# MP3.net
KiCad netlist of a schematic drawn in Altium Designer
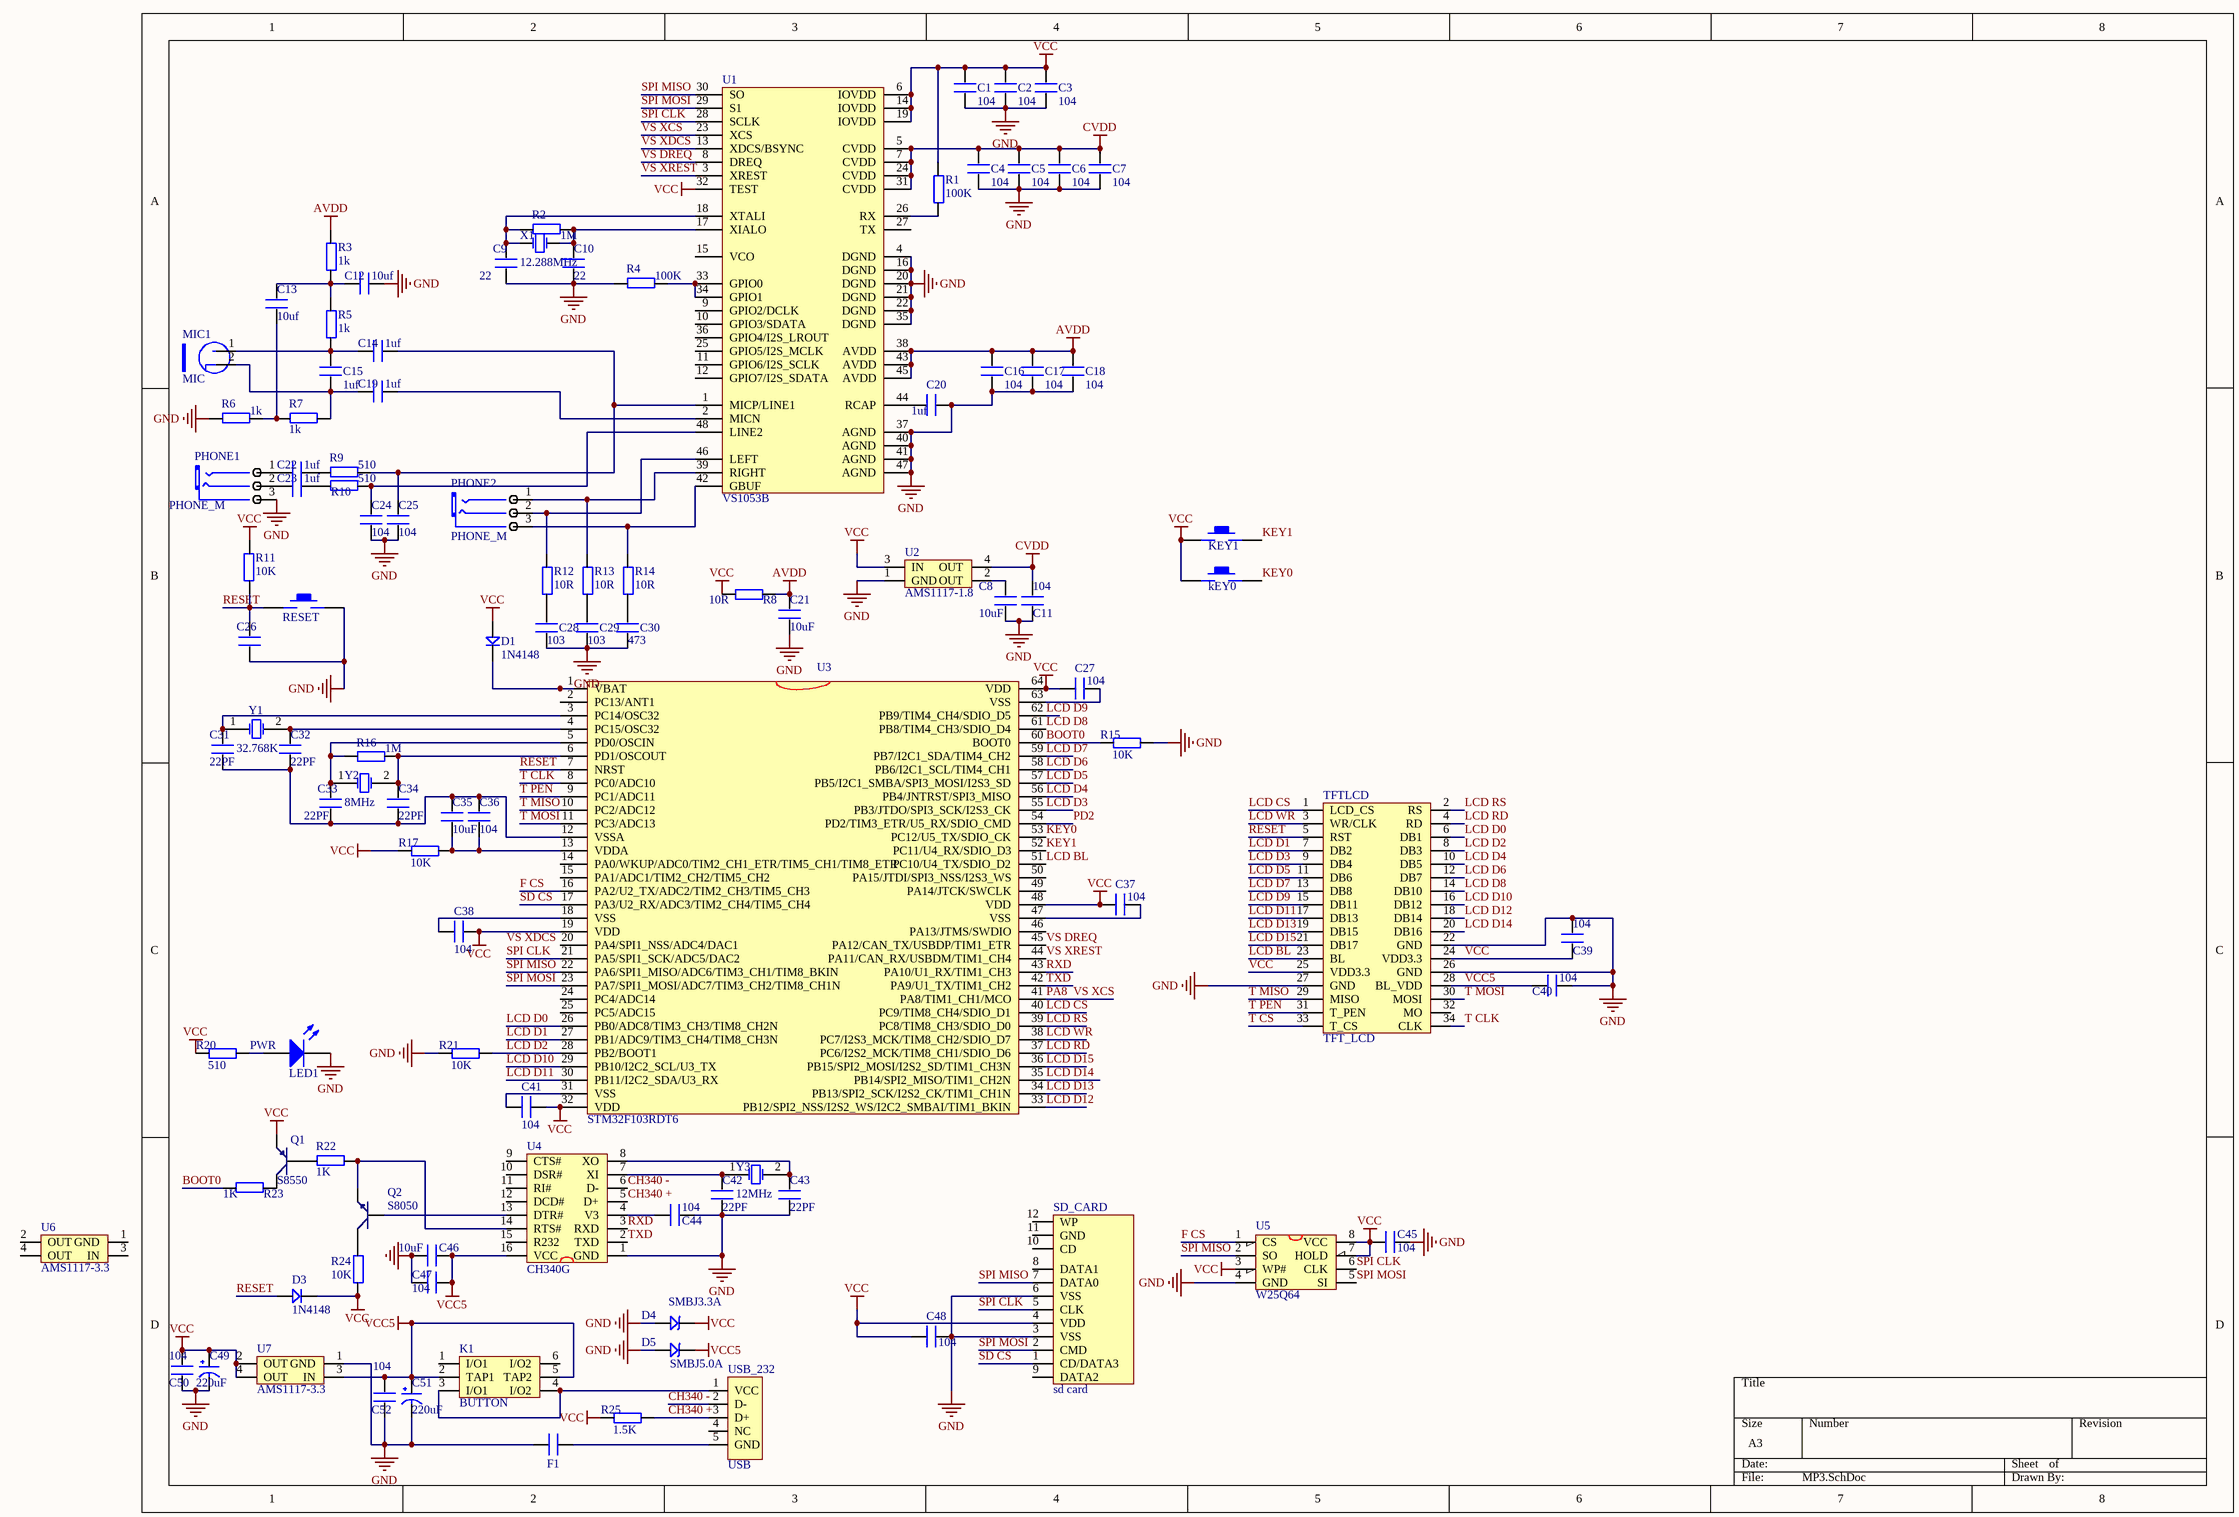
[diagram p0: MP3.SchDoc]

(export (version "E")
  (design (tool "Eeschema 10.0.6"))
  (components
    (comp (ref "C1") (value "104") (footprint "0603P") (libsource (lib "ATK-VS1053 MP3") (part "C")))
    (comp (ref "C2") (value "104") (footprint "0603P") (libsource (lib "ATK-VS1053 MP3") (part "C")))
    (comp (ref "C3") (value "104") (footprint "0603P") (libsource (lib "ATK-VS1053 MP3") (part "C")))
    (comp (ref "C4") (value "104") (footprint "0603P") (libsource (lib "ATK-VS1053 MP3") (part "C")))
    (comp (ref "C5") (value "104") (footprint "0603P") (libsource (lib "ATK-VS1053 MP3") (part "C")))
    (comp (ref "C6") (value "104") (footprint "0603P") (libsource (lib "ATK-VS1053 MP3") (part "C")))
    (comp (ref "C7") (value "104") (footprint "0603P") (libsource (lib "ATK-VS1053 MP3") (part "C")))
    (comp (ref "C8") (value "10uF") (footprint "0603P") (libsource (lib "ATK-MPU6050六轴传感器模块") (part "C")))
    (comp (ref "C9") (value "22") (footprint "0603P") (libsource (lib "ATK-VS1053 MP3") (part "C")))
    (comp (ref "C10") (value "22") (footprint "0603P") (libsource (lib "ATK-VS1053 MP3") (part "C")))
    (comp (ref "C11") (value "104") (footprint "0603P") (libsource (lib "ATK-MPU6050六轴传感器模块") (part "C")))
    (comp (ref "C12") (value "10uf") (footprint "0603P") (libsource (lib "ATK-VS1053 MP3") (part "C")))
    (comp (ref "C13") (value "10uf") (footprint "0603P") (libsource (lib "ATK-VS1053 MP3") (part "C")))
    (comp (ref "C14") (value "1uf") (footprint "0603P") (libsource (lib "ATK-VS1053 MP3") (part "C")))
    (comp (ref "C15") (value "1uf") (footprint "0603P") (libsource (lib "ATK-VS1053 MP3") (part "C")))
    (comp (ref "C16") (value "104") (footprint "0603P") (libsource (lib "ATK-VS1053 MP3") (part "C")))
    (comp (ref "C17") (value "104") (footprint "0603P") (libsource (lib "ATK-VS1053 MP3") (part "C")))
    (comp (ref "C18") (value "104") (footprint "0603P") (libsource (lib "ATK-VS1053 MP3") (part "C")))
    (comp (ref "C19") (value "1uf") (footprint "0603P") (libsource (lib "ATK-VS1053 MP3") (part "C")))
    (comp (ref "C20") (value "1uf") (footprint "0603P") (libsource (lib "ATK-VS1053 MP3") (part "C")))
    (comp (ref "C21") (value "10uF") (footprint "0603P") (libsource (lib "ATK-MPU6050六轴传感器模块") (part "C")))
    (comp (ref "C22") (value "1uf") (footprint "0603P") (libsource (lib "ATK-VS1053 MP3") (part "C")))
    (comp (ref "C23") (value "1uf") (footprint "0603P") (libsource (lib "ATK-VS1053 MP3") (part "C")))
    (comp (ref "C24") (value "104") (footprint "0603P") (libsource (lib "ATK-VS1053 MP3") (part "C")))
    (comp (ref "C25") (value "104") (footprint "0603P") (libsource (lib "ATK-VS1053 MP3") (part "C")))
    (comp (ref "C26") (value "10uF") (footprint "0603P") (libsource (lib "ATK-MPU6050六轴传感器模块") (part "C")))
    (comp (ref "C27") (value "104") (footprint "0603P") (libsource (lib "ATK-MPU6050六轴传感器模块") (part "C")))
    (comp (ref "C28") (value "103") (footprint "0603P") (libsource (lib "ATK-VS1053 MP3") (part "C")))
    (comp (ref "C29") (value "103") (footprint "0603P") (libsource (lib "ATK-VS1053 MP3") (part "C")))
    (comp (ref "C30") (value "473") (footprint "0603P") (libsource (lib "ATK-VS1053 MP3") (part "C")))
    (comp (ref "C31") (value "22PF") (footprint "0603P") (libsource (lib "ATK-MPU6050六轴传感器模块") (part "C")))
    (comp (ref "C32") (value "22PF") (footprint "0603P") (libsource (lib "ATK-MPU6050六轴传感器模块") (part "C")))
    (comp (ref "C33") (value "22PF") (footprint "0603P") (libsource (lib "ATK-MPU6050六轴传感器模块") (part "C")))
    (comp (ref "C34") (value "22PF") (footprint "0603P") (libsource (lib "ATK-MPU6050六轴传感器模块") (part "C")))
    (comp (ref "C35") (value "10uF") (footprint "0603P") (libsource (lib "ATK-MPU6050六轴传感器模块") (part "C")))
    (comp (ref "C36") (value "104") (footprint "0603P") (libsource (lib "ATK-MPU6050六轴传感器模块") (part "C")))
    (comp (ref "C37") (value "104") (footprint "0603P") (libsource (lib "ATK-MPU6050六轴传感器模块") (part "C")))
    (comp (ref "C38") (value "104") (footprint "0603P") (libsource (lib "ATK-MPU6050六轴传感器模块") (part "C")))
    (comp (ref "C39") (value "104") (footprint "0603P") (libsource (lib "ATK-MPU6050六轴传感器模块") (part "C")))
    (comp (ref "C40") (value "104") (footprint "0603P") (libsource (lib "ATK-MPU6050六轴传感器模块") (part "C")))
    (comp (ref "C41") (value "104") (footprint "0603P") (libsource (lib "ATK-MPU6050六轴传感器模块") (part "C")))
    (comp (ref "C42") (value "22PF") (footprint "0603P") (libsource (lib "ATK-MPU6050六轴传感器模块") (part "C")))
    (comp (ref "C43") (value "22PF") (footprint "0603P") (libsource (lib "ATK-MPU6050六轴传感器模块") (part "C")))
    (comp (ref "C44") (value "104") (footprint "0603P") (libsource (lib "ATK-MPU6050六轴传感器模块") (part "C")))
    (comp (ref "C45") (value "104") (footprint "0603P") (libsource (lib "ATK-MPU6050六轴传感器模块") (part "C")))
    (comp (ref "C46") (value "10uF") (footprint "0603P") (libsource (lib "ATK-MPU6050六轴传感器模块") (part "C")))
    (comp (ref "C47") (value "104") (footprint "0603P") (libsource (lib "MiniSTM32 V3.0封装库") (part "C")))
    (comp (ref "C48") (value "104") (footprint "0603P") (libsource (lib "ATK-MPU6050六轴传感器模块") (part "C")))
    (comp (ref "C49")
      (value "220uF")
      (footprint "CC6.56.5")
      (libsource (lib "MiniSTM32 V3.0封装库") (part "CAP"))
    )
    (comp (ref "C50") (value "104") (footprint "0603P") (libsource (lib "ATK-MPU6050六轴传感器模块") (part "C")))
    (comp (ref "C51")
      (value "220uF")
      (footprint "CC6.56.5")
      (libsource (lib "MiniSTM32 V3.0封装库") (part "CAP"))
    )
    (comp (ref "C52") (value "104") (footprint "0603P") (libsource (lib "ATK-MPU6050六轴传感器模块") (part "C")))
    (comp (ref "D1")
      (value "1N4148")
      (footprint "DIODE_SOP")
      (libsource (lib "MiniSTM32 V3.0封装库") (part "D"))
    )
    (comp (ref "D3")
      (value "1N4148")
      (footprint "DIODE_SOP")
      (libsource (lib "MiniSTM32 V3.0封装库") (part "D"))
    )
    (comp (ref "D4")
      (value "SMBJ3.3A")
      (footprint "SMBJ")
      (description "TVS")
      (libsource (lib "MiniSTM32 V3.0封装库") (part "SMBJ"))
    )
    (comp (ref "D5")
      (value "SMBJ5.0A")
      (footprint "SMBJ")
      (description "TVS")
      (libsource (lib "MiniSTM32 V3.0封装库") (part "SMBJ"))
    )
    (comp (ref "F1") (value "104") (footprint "0603P") (libsource (lib "MiniSTM32 V3.0封装库") (part "C")))
    (comp (ref "K1")
      (value "BUTTON")
      (footprint "BTN8.5*8.5")
      (libsource (lib "MiniSTM32 V3.0封装库") (part "BUTTON"))
    )
    (comp (ref "kEY0")
      (value "KEY_M")
      (footprint "KEY_M")
      (libsource (lib "MiniSTM32 V3.0封装库") (part "KEY_M"))
    )
    (comp (ref "KEY1")
      (value "KEY_M")
      (footprint "KEY_M")
      (libsource (lib "MiniSTM32 V3.0封装库") (part "KEY_M"))
    )
    (comp (ref "MIC1") (value "MIC") (footprint "MIC") (libsource (lib "ATK-VS1053 MP3") (part "MIC")))
    (comp (ref "PHONE1")
      (value "PHONE_M")
      (footprint "PHONE_ST")
      (libsource (lib "ATK-VS1053 MP3") (part "PHONE_M"))
    )
    (comp (ref "PHONE2")
      (value "PHONE_M")
      (footprint "PHONE_ST")
      (libsource (lib "ATK-VS1053 MP3") (part "PHONE_M"))
    )
    (comp (ref "PWR")
      (value "LED1")
      (footprint "SMDLED")
      (description "Typical RED, GREEN, YELLOW, AMBER GaAs LED")
      (fields (field (name "PUBLISHER") "Altium Limited"))
      (libsource (lib "MiniSTM32 V3.0封装库") (part "LED2"))
    )
    (comp (ref "Q1")
      (value "S8550")
      (footprint "SOT-23R")
      (description "8550/BCW68")
      (libsource (lib "MiniSTM32 V3.0封装库") (part "PNP"))
    )
    (comp (ref "Q2")
      (value "S8050")
      (footprint "SOT-23R")
      (description "8050/BCW846/BCW847")
      (libsource (lib "MiniSTM32 V3.0封装库") (part "NPN"))
    )
    (comp (ref "R1") (value "100K") (footprint "0603P") (libsource (lib "ATK-MPU6050六轴传感器模块") (part "R")))
    (comp (ref "R2") (value "1M") (footprint "0603P") (libsource (lib "ATK-MPU6050六轴传感器模块") (part "R")))
    (comp (ref "R3") (value "1k") (footprint "0603P") (libsource (lib "ATK-MPU6050六轴传感器模块") (part "R")))
    (comp (ref "R4") (value "100K") (footprint "0603P") (libsource (lib "ATK-MPU6050六轴传感器模块") (part "R")))
    (comp (ref "R5") (value "1k") (footprint "0603P") (libsource (lib "ATK-MPU6050六轴传感器模块") (part "R")))
    (comp (ref "R6") (value "1k") (footprint "0603P") (libsource (lib "ATK-MPU6050六轴传感器模块") (part "R")))
    (comp (ref "R7") (value "1k") (footprint "0603P") (libsource (lib "ATK-MPU6050六轴传感器模块") (part "R")))
    (comp (ref "R8") (value "10R") (footprint "0603P") (libsource (lib "ATK-MPU6050六轴传感器模块") (part "R")))
    (comp (ref "R9") (value "510") (footprint "0603P") (libsource (lib "ATK-MPU6050六轴传感器模块") (part "R")))
    (comp (ref "R10") (value "510") (footprint "0603P") (libsource (lib "ATK-MPU6050六轴传感器模块") (part "R")))
    (comp (ref "R11") (value "10K") (footprint "0603P") (libsource (lib "ATK-MPU6050六轴传感器模块") (part "R")))
    (comp (ref "R12") (value "10R") (footprint "0603P") (libsource (lib "ATK-MPU6050六轴传感器模块") (part "R")))
    (comp (ref "R13") (value "10R") (footprint "0603P") (libsource (lib "ATK-MPU6050六轴传感器模块") (part "R")))
    (comp (ref "R14") (value "10R") (footprint "0603P") (libsource (lib "ATK-MPU6050六轴传感器模块") (part "R")))
    (comp (ref "R15") (value "10K") (footprint "0603P") (libsource (lib "ATK-MPU6050六轴传感器模块") (part "R")))
    (comp (ref "R16") (value "1M") (footprint "0603P") (libsource (lib "MiniSTM32 V3.0封装库") (part "R")))
    (comp (ref "R17") (value "10K") (footprint "0603P") (libsource (lib "ATK-MPU6050六轴传感器模块") (part "R")))
    (comp (ref "R20") (value "510") (footprint "0603P") (libsource (lib "ATK-MPU6050六轴传感器模块") (part "R")))
    (comp (ref "R21") (value "10K") (footprint "0603P") (libsource (lib "ATK-MPU6050六轴传感器模块") (part "R")))
    (comp (ref "R22") (value "1K") (footprint "0603P") (libsource (lib "ATK-MPU6050六轴传感器模块") (part "R")))
    (comp (ref "R23") (value "1K") (footprint "0603P") (libsource (lib "ATK-MPU6050六轴传感器模块") (part "R")))
    (comp (ref "R24") (value "10K") (footprint "0603P") (libsource (lib "ATK-MPU6050六轴传感器模块") (part "R")))
    (comp (ref "R25") (value "1.5K") (footprint "0603P") (libsource (lib "ATK-MPU6050六轴传感器模块") (part "R")))
    (comp (ref "RESET")
      (value "KEY_M")
      (footprint "KEY_M")
      (libsource (lib "MiniSTM32 V3.0封装库") (part "KEY_M"))
    )
    (comp (ref "SD_CARD")
      (value "sd card")
      (footprint "SDCARD_L")
      (libsource (lib "MiniSTM32 V3.0封装库") (part "sd card"))
    )
    (comp (ref "TFTLCD")
      (value "TFT_LCD")
      (footprint "HDR2X17")
      (libsource (lib "MiniSTM32 V3.0封装库") (part "TFT_LCD"))
    )
    (comp (ref "U1")
      (value "VS1053B")
      (footprint "mTQFP48")
      (libsource (lib "ATK-VS1053 MP3") (part "VS1053"))
    )
    (comp (ref "U2")
      (value "AMS1117-1.8")
      (footprint "AMS1117")
      (libsource (lib "ATK-VS1053 MP3") (part "AMS1117"))
    )
    (comp (ref "U3")
      (value "STM32F103RDT6")
      (footprint "LQFP64")
      (libsource (lib "stm32") (part "STM32F103RDT6"))
    )
    (comp (ref "U4")
      (value "CH340G")
      (footprint "SOP16M")
      (description "USB2UART")
      (libsource (lib "MiniSTM32 V3.0封装库") (part "CH340G"))
    )
    (comp (ref "U5")
      (value "W25Q64")
      (footprint "SOIC-8")
      (description "W25X16;SST25VF016;MX25L1605")
      (libsource (lib "MiniSTM32 V3.0封装库") (part "W25X16"))
    )
    (comp (ref "U6")
      (value "AMS1117-3.3")
      (footprint "AMS1117")
      (libsource (lib "MiniSTM32 V3.0封装库") (part "AMS1117"))
    )
    (comp (ref "U7")
      (value "AMS1117-3.3")
      (footprint "AMS1117")
      (libsource (lib "MiniSTM32 V3.0封装库") (part "AMS1117"))
    )
    (comp (ref "USB_232")
      (value "USB")
      (footprint "USB/SM0.8-6H5")
      (libsource (lib "MiniSTM32 V3.0封装库") (part "USB5"))
    )
    (comp (ref "X1")
      (value "12.288MHz")
      (footprint "XTAL_US")
      (description "Crystal Oscillator")
      (fields (field (name "PUBLISHER") "Altium Limited"))
      (libsource (lib "ATK-VS1053 MP3") (part "XTAL"))
    )
    (comp (ref "Y1")
      (value "32.768K")
      (footprint "R38")
      (description "Crystal Oscillator")
      (fields (field (name "PUBLISHER") "Altium Limited"))
      (libsource (lib "Miscellaneous Devices") (part "XTAL"))
    )
    (comp (ref "Y2")
      (value "8MHz")
      (footprint "XTAL_US")
      (description "Crystal Oscillator")
      (fields (field (name "PUBLISHER") "Altium Limited"))
      (libsource (lib "MiniSTM32 V3.0封装库") (part "XTAL"))
    )
    (comp (ref "Y3")
      (value "12MHz")
      (footprint "XTAL_US")
      (description "Crystal Oscillator")
      (fields (field (name "PUBLISHER") "Altium Limited"))
      (libsource (lib "MiniSTM32 V3.0封装库") (part "XTAL"))
    )
  )
  (nets
    (net (code "1") (name "/BOOT0") (class "Default")
      (node (ref "R15") (pin "1") (pintype "passive"))
      (node (ref "R23") (pin "2") (pintype "passive"))
      (node (ref "U3") (pin "60") (pinfunction "BOOT0_60") (pintype "passive"))
    )
    (net (code "2") (name "/CH340 +") (class "Default")
      (node (ref "R25") (pin "2") (pintype "passive"))
      (node (ref "U4") (pin "5") (pinfunction "D+_5") (pintype "passive"))
      (node (ref "USB_232") (pin "3") (pinfunction "D+_3") (pintype "passive"))
    )
    (net (code "3") (name "/CH340 -") (class "Default")
      (node (ref "U4") (pin "6") (pinfunction "D-_6") (pintype "passive"))
      (node (ref "USB_232") (pin "2") (pinfunction "D-_2") (pintype "passive"))
    )
    (net (code "4") (name "/F CS") (class "Default")
      (node (ref "U3") (pin "16") (pinfunction "PA2/U2_TX/ADC2/TIM2_CH3/TIM5_CH3_16") (pintype "passive"))
      (node (ref "U5") (pin "1") (pinfunction "CS_1") (pintype "passive"))
    )
    (net (code "5") (name "/KEY0") (class "Default")
      (node (ref "U3") (pin "53") (pinfunction "PC12/U5_TX/SDIO_CK_53") (pintype "passive"))
      (node (ref "kEY0") (pin "2") (pinfunction "2_2") (pintype "passive"))
    )
    (net (code "6") (name "/KEY1") (class "Default")
      (node (ref "KEY1") (pin "2") (pinfunction "2_2") (pintype "passive"))
      (node (ref "U3") (pin "52") (pinfunction "PC11/U4_RX/SDIO_D3_52") (pintype "passive"))
    )
    (net (code "7") (name "/LCD BL") (class "Default")
      (node (ref "TFTLCD") (pin "23") (pinfunction "BL_23") (pintype "passive"))
      (node (ref "U3") (pin "51") (pinfunction "PC10/U4_TX/SDIO_D2_51") (pintype "passive"))
    )
    (net (code "8") (name "/LCD CS") (class "Default")
      (node (ref "TFTLCD") (pin "1") (pinfunction "LCD_CS_1") (pintype "passive"))
      (node (ref "U3") (pin "40") (pinfunction "PC9/TIM8_CH4/SDIO_D1_40") (pintype "passive"))
    )
    (net (code "9") (name "/LCD D0") (class "Default")
      (node (ref "TFTLCD") (pin "6") (pinfunction "DB1_6") (pintype "passive"))
      (node (ref "U3") (pin "26") (pinfunction "PB0/ADC8/TIM3_CH3/TIM8_CH2N_26") (pintype "passive"))
    )
    (net (code "10") (name "/LCD D1") (class "Default")
      (node (ref "TFTLCD") (pin "7") (pinfunction "DB2_7") (pintype "passive"))
      (node (ref "U3") (pin "27") (pinfunction "PB1/ADC9/TIM3_CH4/TIM8_CH3N_27") (pintype "passive"))
    )
    (net (code "11") (name "/LCD D2") (class "Default")
      (node (ref "R21") (pin "2") (pintype "passive"))
      (node (ref "TFTLCD") (pin "8") (pinfunction "DB3_8") (pintype "passive"))
      (node (ref "U3") (pin "28") (pinfunction "PB2/BOOT1_28") (pintype "passive"))
    )
    (net (code "12") (name "/LCD D3") (class "Default")
      (node (ref "TFTLCD") (pin "9") (pinfunction "DB4_9") (pintype "passive"))
      (node (ref "U3") (pin "55") (pinfunction "PB3/JTDO/SPI3_SCK/I2S3_CK_55") (pintype "passive"))
    )
    (net (code "13") (name "/LCD D4") (class "Default")
      (node (ref "TFTLCD") (pin "10") (pinfunction "DB5_10") (pintype "passive"))
      (node (ref "U3") (pin "56") (pinfunction "PB4/JNTRST/SPI3_MISO_56") (pintype "passive"))
    )
    (net (code "14") (name "/LCD D5") (class "Default")
      (node (ref "TFTLCD") (pin "11") (pinfunction "DB6_11") (pintype "passive"))
      (node (ref "U3") (pin "57") (pinfunction "PB5/I2C1_SMBA/SPI3_MOSI/I2S3_SD_57") (pintype "passive"))
    )
    (net (code "15") (name "/LCD D6") (class "Default")
      (node (ref "TFTLCD") (pin "12") (pinfunction "DB7_12") (pintype "passive"))
      (node (ref "U3") (pin "58") (pinfunction "PB6/I2C1_SCL/TIM4_CH1_58") (pintype "passive"))
    )
    (net (code "16") (name "/LCD D7") (class "Default")
      (node (ref "TFTLCD") (pin "13") (pinfunction "DB8_13") (pintype "passive"))
      (node (ref "U3") (pin "59") (pinfunction "PB7/I2C1_SDA/TIM4_CH2_59") (pintype "passive"))
    )
    (net (code "17") (name "/LCD D8") (class "Default")
      (node (ref "TFTLCD") (pin "14") (pinfunction "DB10_14") (pintype "passive"))
      (node (ref "U3") (pin "61") (pinfunction "PB8/TIM4_CH3/SDIO_D4_61") (pintype "passive"))
    )
    (net (code "18") (name "/LCD D9") (class "Default")
      (node (ref "TFTLCD") (pin "15") (pinfunction "DB11_15") (pintype "passive"))
      (node (ref "U3") (pin "62") (pinfunction "PB9/TIM4_CH4/SDIO_D5_62") (pintype "passive"))
    )
    (net (code "19") (name "/LCD D10") (class "Default")
      (node (ref "TFTLCD") (pin "16") (pinfunction "DB12_16") (pintype "passive"))
      (node (ref "U3") (pin "29") (pinfunction "PB10/I2C2_SCL/U3_TX_29") (pintype "passive"))
    )
    (net (code "20") (name "/LCD D11") (class "Default")
      (node (ref "TFTLCD") (pin "17") (pinfunction "DB13_17") (pintype "passive"))
      (node (ref "U3") (pin "30") (pinfunction "PB11/I2C2_SDA/U3_RX_30") (pintype "passive"))
    )
    (net (code "21") (name "/LCD D12") (class "Default")
      (node (ref "TFTLCD") (pin "18") (pinfunction "DB14_18") (pintype "passive"))
      (node (ref "U3") (pin "33") (pinfunction "PB12/SPI2_NSS/I2S2_WS/I2C2_SMBAI/TIM1_BKIN_33") (pintype "passive"))
    )
    (net (code "22") (name "/LCD D13") (class "Default")
      (node (ref "TFTLCD") (pin "19") (pinfunction "DB15_19") (pintype "passive"))
      (node (ref "U3") (pin "34") (pinfunction "PB13/SPI2_SCK/I2S2_CK/TIM1_CH1N_34") (pintype "passive"))
    )
    (net (code "23") (name "/LCD D14") (class "Default")
      (node (ref "TFTLCD") (pin "20") (pinfunction "DB16_20") (pintype "passive"))
      (node (ref "U3") (pin "35") (pinfunction "PB14/SPI2_MISO/TIM1_CH2N_35") (pintype "passive"))
    )
    (net (code "24") (name "/LCD D15") (class "Default")
      (node (ref "TFTLCD") (pin "21") (pinfunction "DB17_21") (pintype "passive"))
      (node (ref "U3") (pin "36") (pinfunction "PB15/SPI2_MOSI/I2S2_SD/TIM1_CH3N_36") (pintype "passive"))
    )
    (net (code "25") (name "/LCD RD") (class "Default")
      (node (ref "TFTLCD") (pin "4") (pinfunction "RD_4") (pintype "passive"))
      (node (ref "U3") (pin "37") (pinfunction "PC6/I2S2_MCK/TIM8_CH1/SDIO_D6_37") (pintype "passive"))
    )
    (net (code "26") (name "/LCD RS") (class "Default")
      (node (ref "TFTLCD") (pin "2") (pinfunction "RS_2") (pintype "passive"))
      (node (ref "U3") (pin "39") (pinfunction "PC8/TIM8_CH3/SDIO_D0_39") (pintype "passive"))
    )
    (net (code "27") (name "/LCD WR") (class "Default")
      (node (ref "TFTLCD") (pin "3") (pinfunction "WR/CLK_3") (pintype "passive"))
      (node (ref "U3") (pin "38") (pinfunction "PC7/I2S3_MCK/TIM8_CH2/SDIO_D7_38") (pintype "passive"))
    )
    (net (code "28") (name "/PA8") (class "Default")
      (node (ref "U1") (pin "23") (pinfunction "XCS_23") (pintype "passive"))
      (node (ref "U3") (pin "41") (pinfunction "PA8/TIM1_CH1/MCO_41") (pintype "passive"))
    )
    (net (code "29") (name "/PD2") (class "Default")
      (node (ref "U3") (pin "54") (pinfunction "PD2/TIM3_ETR/U5_RX/SDIO_CMD_54") (pintype "passive"))
    )
    (net (code "30") (name "/RESET") (class "Default")
      (node (ref "C26") (pin "2") (pintype "passive"))
      (node (ref "D3") (pin "1") (pintype "passive"))
      (node (ref "R11") (pin "2") (pintype "passive"))
      (node (ref "RESET") (pin "1") (pinfunction "1_1") (pintype "passive"))
      (node (ref "TFTLCD") (pin "5") (pinfunction "RST_5") (pintype "passive"))
      (node (ref "U3") (pin "7") (pinfunction "NRST_7") (pintype "passive"))
    )
    (net (code "31") (name "/RXD") (class "Default")
      (node (ref "U3") (pin "43") (pinfunction "PA10/U1_RX/TIM1_CH3_43") (pintype "passive"))
      (node (ref "U4") (pin "3") (pinfunction "RXD_3") (pintype "passive"))
    )
    (net (code "32") (name "/SD CS") (class "Default")
      (node (ref "SD_CARD") (pin "1") (pinfunction "CD/DATA3_1") (pintype "passive"))
      (node (ref "U3") (pin "17") (pinfunction "PA3/U2_RX/ADC3/TIM2_CH4/TIM5_CH4_17") (pintype "passive"))
    )
    (net (code "33") (name "/SPI CLK") (class "Default")
      (node (ref "SD_CARD") (pin "5") (pinfunction "CLK_5") (pintype "passive"))
      (node (ref "U1") (pin "28") (pinfunction "SCLK_28") (pintype "passive"))
      (node (ref "U3") (pin "21") (pinfunction "PA5/SPI1_SCK/ADC5/DAC2_21") (pintype "passive"))
      (node (ref "U5") (pin "6") (pinfunction "CLK_6") (pintype "passive"))
    )
    (net (code "34") (name "/SPI MISO") (class "Default")
      (node (ref "SD_CARD") (pin "7") (pinfunction "DATA0_7") (pintype "passive"))
      (node (ref "U1") (pin "30") (pinfunction "SO_30") (pintype "passive"))
      (node (ref "U3") (pin "22") (pinfunction "PA6/SPI1_MISO/ADC6/TIM3_CH1/TIM8_BKIN_22") (pintype "passive"))
      (node (ref "U5") (pin "2") (pinfunction "SO_2") (pintype "passive"))
    )
    (net (code "35") (name "/SPI MOSI") (class "Default")
      (node (ref "SD_CARD") (pin "2") (pinfunction "CMD_2") (pintype "passive"))
      (node (ref "U1") (pin "29") (pinfunction "S1_29") (pintype "passive"))
      (node (ref "U3") (pin "23") (pinfunction "PA7/SPI1_MOSI/ADC7/TIM3_CH2/TIM8_CH1N_23") (pintype "passive"))
      (node (ref "U5") (pin "5") (pinfunction "SI_5") (pintype "passive"))
    )
    (net (code "36") (name "/T CLK") (class "Default")
      (node (ref "TFTLCD") (pin "34") (pinfunction "CLK_34") (pintype "passive"))
      (node (ref "U3") (pin "8") (pinfunction "PC0/ADC10_8") (pintype "passive"))
    )
    (net (code "37") (name "/T CS") (class "Default")
      (node (ref "TFTLCD") (pin "33") (pinfunction "T_CS_33") (pintype "passive"))
    )
    (net (code "38") (name "/T MISO") (class "Default")
      (node (ref "TFTLCD") (pin "29") (pinfunction "MISO_29") (pintype "passive"))
      (node (ref "U3") (pin "10") (pinfunction "PC2/ADC12_10") (pintype "passive"))
    )
    (net (code "39") (name "/T MOSI") (class "Default")
      (node (ref "TFTLCD") (pin "30") (pinfunction "MOSI_30") (pintype "passive"))
      (node (ref "U3") (pin "11") (pinfunction "PC3/ADC13_11") (pintype "passive"))
    )
    (net (code "40") (name "/T PEN") (class "Default")
      (node (ref "TFTLCD") (pin "31") (pinfunction "T_PEN_31") (pintype "passive"))
      (node (ref "U3") (pin "9") (pinfunction "PC1/ADC11_9") (pintype "passive"))
    )
    (net (code "41") (name "/TXD") (class "Default")
      (node (ref "U3") (pin "42") (pinfunction "PA9/U1_TX/TIM1_CH2_42") (pintype "passive"))
      (node (ref "U4") (pin "2") (pinfunction "TXD_2") (pintype "passive"))
    )
    (net (code "42") (name "/VS DREQ") (class "Default")
      (node (ref "U1") (pin "8") (pinfunction "DREQ_8") (pintype "passive"))
      (node (ref "U3") (pin "45") (pinfunction "PA12/CAN_TX/USBDP/TIM1_ETR_45") (pintype "passive"))
    )
    (net (code "43") (name "/VS XDCS") (class "Default")
      (node (ref "U1") (pin "13") (pinfunction "XDCS/BSYNC_13") (pintype "passive"))
    )
    (net (code "44") (name "/VS XREST") (class "Default")
      (node (ref "U1") (pin "3") (pinfunction "XREST_3") (pintype "passive"))
      (node (ref "U3") (pin "44") (pinfunction "PA11/CAN_RX/USBDM/TIM1_CH4_44") (pintype "passive"))
    )
    (net (code "45") (name "AVDD") (class "Default")
      (node (ref "C16") (pin "2") (pintype "passive"))
      (node (ref "C17") (pin "2") (pintype "passive"))
      (node (ref "C18") (pin "2") (pintype "passive"))
      (node (ref "C21") (pin "1") (pintype "passive"))
      (node (ref "R3") (pin "2") (pintype "passive"))
      (node (ref "R8") (pin "2") (pintype "passive"))
      (node (ref "U1") (pin "38") (pinfunction "AVDD_38") (pintype "passive"))
      (node (ref "U1") (pin "43") (pinfunction "AVDD_43") (pintype "passive"))
      (node (ref "U1") (pin "45") (pinfunction "AVDD_45") (pintype "passive"))
    )
    (net (code "46") (name "CVDD") (class "Default")
      (node (ref "C11") (pin "1") (pintype "passive"))
      (node (ref "C4") (pin "2") (pintype "passive"))
      (node (ref "C5") (pin "2") (pintype "passive"))
      (node (ref "C6") (pin "2") (pintype "passive"))
      (node (ref "C7") (pin "2") (pintype "passive"))
      (node (ref "U1") (pin "24") (pinfunction "CVDD_24") (pintype "passive"))
      (node (ref "U1") (pin "31") (pinfunction "CVDD_31") (pintype "passive"))
      (node (ref "U1") (pin "5") (pinfunction "CVDD_5") (pintype "passive"))
      (node (ref "U1") (pin "7") (pinfunction "CVDD_7") (pintype "passive"))
      (node (ref "U2") (pin "4") (pinfunction "OUT_4") (pintype "passive"))
    )
    (net (code "47") (name "GND") (class "Default")
      (node (ref "C1") (pin "1") (pintype "passive"))
      (node (ref "C10") (pin "2") (pintype "passive"))
      (node (ref "C11") (pin "2") (pintype "passive"))
      (node (ref "C12") (pin "1") (pintype "passive"))
      (node (ref "C16") (pin "1") (pintype "passive"))
      (node (ref "C17") (pin "1") (pintype "passive"))
      (node (ref "C18") (pin "1") (pintype "passive"))
      (node (ref "C2") (pin "1") (pintype "passive"))
      (node (ref "C20") (pin "1") (pintype "passive"))
      (node (ref "C21") (pin "2") (pintype "passive"))
      (node (ref "C24") (pin "1") (pintype "passive"))
      (node (ref "C25") (pin "1") (pintype "passive"))
      (node (ref "C26") (pin "1") (pintype "passive"))
      (node (ref "C28") (pin "1") (pintype "passive"))
      (node (ref "C29") (pin "1") (pintype "passive"))
      (node (ref "C3") (pin "1") (pintype "passive"))
      (node (ref "C30") (pin "1") (pintype "passive"))
      (node (ref "C39") (pin "1") (pintype "passive"))
      (node (ref "C4") (pin "1") (pintype "passive"))
      (node (ref "C40") (pin "2") (pintype "passive"))
      (node (ref "C42") (pin "1") (pintype "passive"))
      (node (ref "C43") (pin "1") (pintype "passive"))
      (node (ref "C44") (pin "2") (pintype "passive"))
      (node (ref "C45") (pin "1") (pintype "passive"))
      (node (ref "C46") (pin "1") (pintype "passive"))
      (node (ref "C47") (pin "2") (pintype "passive"))
      (node (ref "C48") (pin "1") (pintype "passive"))
      (node (ref "C49") (pin "2") (pinfunction "GND_2") (pintype "passive"))
      (node (ref "C5") (pin "1") (pintype "passive"))
      (node (ref "C50") (pin "2") (pintype "passive"))
      (node (ref "C51") (pin "2") (pinfunction "GND_2") (pintype "passive"))
      (node (ref "C52") (pin "2") (pintype "passive"))
      (node (ref "C6") (pin "1") (pintype "passive"))
      (node (ref "C7") (pin "1") (pintype "passive"))
      (node (ref "C8") (pin "2") (pintype "passive"))
      (node (ref "C9") (pin "2") (pintype "passive"))
      (node (ref "D4") (pin "1") (pintype "passive"))
      (node (ref "D5") (pin "1") (pintype "passive"))
      (node (ref "F1") (pin "2") (pintype "passive"))
      (node (ref "PHONE1") (pin "3") (pinfunction "COM_3") (pintype "passive"))
      (node (ref "PWR") (pin "2") (pinfunction "K_2") (pintype "passive"))
      (node (ref "R15") (pin "2") (pintype "passive"))
      (node (ref "R21") (pin "1") (pintype "passive"))
      (node (ref "R4") (pin "2") (pintype "passive"))
      (node (ref "R6") (pin "2") (pintype "passive"))
      (node (ref "RESET") (pin "2") (pinfunction "2_2") (pintype "passive"))
      (node (ref "SD_CARD") (pin "3") (pinfunction "VSS_3") (pintype "passive"))
      (node (ref "SD_CARD") (pin "6") (pinfunction "VSS_6") (pintype "passive"))
      (node (ref "TFTLCD") (pin "22") (pinfunction "GND_22") (pintype "passive"))
      (node (ref "TFTLCD") (pin "26") (pinfunction "GND_26") (pintype "passive"))
      (node (ref "TFTLCD") (pin "27") (pinfunction "GND_27") (pintype "passive"))
      (node (ref "U1") (pin "16") (pinfunction "DGND_16") (pintype "passive"))
      (node (ref "U1") (pin "20") (pinfunction "DGND_20") (pintype "passive"))
      (node (ref "U1") (pin "21") (pinfunction "DGND_21") (pintype "passive"))
      (node (ref "U1") (pin "22") (pinfunction "DGND_22") (pintype "passive"))
      (node (ref "U1") (pin "35") (pinfunction "DGND_35") (pintype "passive"))
      (node (ref "U1") (pin "37") (pinfunction "AGND_37") (pintype "passive"))
      (node (ref "U1") (pin "4") (pinfunction "DGND_4") (pintype "passive"))
      (node (ref "U1") (pin "40") (pinfunction "AGND_40") (pintype "passive"))
      (node (ref "U1") (pin "41") (pinfunction "AGND_41") (pintype "passive"))
      (node (ref "U1") (pin "47") (pinfunction "AGND_47") (pintype "passive"))
      (node (ref "U2") (pin "1") (pinfunction "GND_1") (pintype "passive"))
      (node (ref "U4") (pin "1") (pinfunction "GND_1") (pintype "passive"))
      (node (ref "U5") (pin "4") (pinfunction "GND_4") (pintype "passive"))
      (node (ref "U7") (pin "1") (pinfunction "GND_1") (pintype "passive"))
    )
    (net (code "48") (name "Net-(C8-Pad1)") (class "Default")
      (node (ref "C8") (pin "1") (pintype "passive"))
      (node (ref "U2") (pin "2") (pinfunction "OUT_2") (pintype "passive"))
    )
    (net (code "49") (name "Net-(C12-Pad2)") (class "Default")
      (node (ref "C12") (pin "2") (pintype "passive"))
      (node (ref "C13") (pin "1") (pintype "passive"))
      (node (ref "R3") (pin "1") (pintype "passive"))
      (node (ref "R5") (pin "2") (pintype "passive"))
    )
    (net (code "50") (name "Net-(C13-Pad2)") (class "Default")
      (node (ref "C13") (pin "2") (pintype "passive"))
      (node (ref "R6") (pin "1") (pintype "passive"))
      (node (ref "R7") (pin "2") (pintype "passive"))
    )
    (net (code "51") (name "Net-(C22-Pad1)") (class "Default")
      (node (ref "C22") (pin "1") (pintype "passive"))
      (node (ref "R9") (pin "2") (pintype "passive"))
    )
    (net (code "52") (name "Net-(C23-Pad1)") (class "Default")
      (node (ref "C23") (pin "1") (pintype "passive"))
      (node (ref "R10") (pin "2") (pintype "passive"))
    )
    (net (code "53") (name "Net-(C27-Pad1)") (class "Default")
      (node (ref "C27") (pin "1") (pintype "passive"))
      (node (ref "U3") (pin "63") (pinfunction "VSS_63") (pintype "passive"))
    )
    (net (code "54") (name "Net-(C28-Pad2)") (class "Default")
      (node (ref "C28") (pin "2") (pintype "passive"))
      (node (ref "R12") (pin "1") (pintype "passive"))
    )
    (net (code "55") (name "Net-(C29-Pad2)") (class "Default")
      (node (ref "C29") (pin "2") (pintype "passive"))
      (node (ref "R13") (pin "1") (pintype "passive"))
    )
    (net (code "56") (name "Net-(C30-Pad2)") (class "Default")
      (node (ref "C30") (pin "2") (pintype "passive"))
      (node (ref "R14") (pin "1") (pintype "passive"))
    )
    (net (code "57") (name "Net-(C37-Pad1)") (class "Default")
      (node (ref "C37") (pin "1") (pintype "passive"))
      (node (ref "U3") (pin "47") (pinfunction "VSS_47") (pintype "passive"))
    )
    (net (code "58") (name "Net-(C38-Pad2)") (class "Default")
      (node (ref "C38") (pin "2") (pintype "passive"))
      (node (ref "U3") (pin "18") (pinfunction "VSS_18") (pintype "passive"))
    )
    (net (code "59") (name "Net-(C41-Pad2)") (class "Default")
      (node (ref "C41") (pin "2") (pintype "passive"))
      (node (ref "U3") (pin "31") (pinfunction "VSS_31") (pintype "passive"))
    )
    (net (code "60") (name "Net-(MIC1-GND)") (class "Default")
      (node (ref "C15") (pin "2") (pintype "passive"))
      (node (ref "C19") (pin "2") (pintype "passive"))
      (node (ref "MIC1") (pin "2") (pinfunction "GND_2") (pintype "passive"))
      (node (ref "R7") (pin "1") (pintype "passive"))
    )
    (net (code "61") (name "Net-(MIC1-VCC)") (class "Default")
      (node (ref "C14") (pin "2") (pintype "passive"))
      (node (ref "C15") (pin "1") (pintype "passive"))
      (node (ref "MIC1") (pin "1") (pinfunction "VCC_1") (pintype "passive"))
      (node (ref "R5") (pin "1") (pintype "passive"))
    )
    (net (code "62") (name "Net-(PHONE1-CHL)") (class "Default")
      (node (ref "C22") (pin "2") (pintype "passive"))
      (node (ref "PHONE1") (pin "1") (pinfunction "CHL_1") (pintype "passive"))
    )
    (net (code "63") (name "Net-(PHONE1-CHR)") (class "Default")
      (node (ref "C23") (pin "2") (pintype "passive"))
      (node (ref "PHONE1") (pin "2") (pinfunction "CHR_2") (pintype "passive"))
    )
    (net (code "64") (name "Net-(PHONE2-CHL)") (class "Default")
      (node (ref "PHONE2") (pin "1") (pinfunction "CHL_1") (pintype "passive"))
      (node (ref "R13") (pin "2") (pintype "passive"))
      (node (ref "U1") (pin "39") (pinfunction "RIGHT_39") (pintype "passive"))
    )
    (net (code "65") (name "Net-(PHONE2-CHR)") (class "Default")
      (node (ref "PHONE2") (pin "2") (pinfunction "CHR_2") (pintype "passive"))
      (node (ref "R12") (pin "2") (pintype "passive"))
      (node (ref "U1") (pin "46") (pinfunction "LEFT_46") (pintype "passive"))
    )
    (net (code "66") (name "Net-(PHONE2-COM)") (class "Default")
      (node (ref "PHONE2") (pin "3") (pinfunction "COM_3") (pintype "passive"))
      (node (ref "R14") (pin "2") (pintype "passive"))
      (node (ref "U1") (pin "42") (pinfunction "GBUF_42") (pintype "passive"))
    )
    (net (code "67") (name "Net-(PWR-A)") (class "Default")
      (node (ref "PWR") (pin "1") (pinfunction "A_1") (pintype "passive"))
      (node (ref "R20") (pin "2") (pintype "passive"))
    )
    (net (code "68") (name "Net-(Q1-B)") (class "Default")
      (node (ref "Q1") (pin "2") (pinfunction "B_2") (pintype "passive"))
      (node (ref "R22") (pin "2") (pintype "passive"))
    )
    (net (code "69") (name "Net-(Q1-C)") (class "Default")
      (node (ref "Q1") (pin "3") (pinfunction "C_3") (pintype "passive"))
      (node (ref "R23") (pin "1") (pintype "passive"))
    )
    (net (code "70") (name "Net-(Q2-B)") (class "Default")
      (node (ref "Q2") (pin "2") (pinfunction "B_2") (pintype "passive"))
      (node (ref "U4") (pin "13") (pinfunction "DTR#_13") (pintype "passive"))
    )
    (net (code "71") (name "Net-(Q2-C)") (class "Default")
      (node (ref "Q2") (pin "3") (pinfunction "C_3") (pintype "passive"))
      (node (ref "R24") (pin "2") (pintype "passive"))
    )
    (net (code "72") (name "Net-(Q2-E)") (class "Default")
      (node (ref "Q2") (pin "1") (pinfunction "E_1") (pintype "passive"))
      (node (ref "R22") (pin "1") (pintype "passive"))
      (node (ref "U4") (pin "14") (pinfunction "RTS#_14") (pintype "passive"))
    )
    (net (code "73") (name "Net-(U1-GPIO0)") (class "Default")
      (node (ref "R4") (pin "1") (pintype "passive"))
      (node (ref "U1") (pin "33") (pinfunction "GPIO0_33") (pintype "passive"))
      (node (ref "U1") (pin "34") (pinfunction "GPIO1_34") (pintype "passive"))
    )
    (net (code "74") (name "Net-(U1-LINE2)") (class "Default")
      (node (ref "C24") (pin "2") (pintype "passive"))
      (node (ref "R10") (pin "1") (pintype "passive"))
      (node (ref "U1") (pin "48") (pinfunction "LINE2_48") (pintype "passive"))
    )
    (net (code "75") (name "Net-(U1-MICN)") (class "Default")
      (node (ref "C19") (pin "1") (pintype "passive"))
      (node (ref "U1") (pin "2") (pinfunction "MICN_2") (pintype "passive"))
    )
    (net (code "76") (name "Net-(U1-MICP{slash}LINE1)") (class "Default")
      (node (ref "C14") (pin "1") (pintype "passive"))
      (node (ref "C25") (pin "2") (pintype "passive"))
      (node (ref "R9") (pin "1") (pintype "passive"))
      (node (ref "U1") (pin "1") (pinfunction "MICP/LINE1_1") (pintype "passive"))
    )
    (net (code "77") (name "Net-(U1-RCAP)") (class "Default")
      (node (ref "C20") (pin "2") (pintype "passive"))
      (node (ref "U1") (pin "44") (pinfunction "RCAP_44") (pintype "passive"))
    )
    (net (code "78") (name "Net-(U1-RX)") (class "Default")
      (node (ref "R1") (pin "1") (pintype "passive"))
      (node (ref "U1") (pin "26") (pinfunction "RX_26") (pintype "passive"))
    )
    (net (code "79") (name "Net-(U1-XIALO)") (class "Default")
      (node (ref "C10") (pin "1") (pintype "passive"))
      (node (ref "R2") (pin "1") (pintype "passive"))
      (node (ref "U1") (pin "17") (pinfunction "XIALO_17") (pintype "passive"))
      (node (ref "X1") (pin "2") (pinfunction "OSC2_2") (pintype "passive"))
    )
    (net (code "80") (name "Net-(U1-XTALI)") (class "Default")
      (node (ref "C9") (pin "1") (pintype "passive"))
      (node (ref "R2") (pin "2") (pintype "passive"))
      (node (ref "U1") (pin "18") (pinfunction "XTALI_18") (pintype "passive"))
      (node (ref "X1") (pin "1") (pinfunction "OSC1_1") (pintype "passive"))
    )
    (net (code "81") (name "Net-(U3-PC14{slash}OSC32)") (class "Default")
      (node (ref "C31") (pin "2") (pintype "passive"))
      (node (ref "U3") (pin "3") (pinfunction "PC14/OSC32_3") (pintype "passive"))
      (node (ref "Y1") (pin "1") (pinfunction "OSC1_1") (pintype "passive"))
    )
    (net (code "82") (name "Net-(U3-PC15{slash}OSC32)") (class "Default")
      (node (ref "C32") (pin "2") (pintype "passive"))
      (node (ref "U3") (pin "4") (pinfunction "PC15/OSC32_4") (pintype "passive"))
      (node (ref "Y1") (pin "2") (pinfunction "OSC2_2") (pintype "passive"))
    )
    (net (code "83") (name "Net-(U3-PD0{slash}OSCIN)") (class "Default")
      (node (ref "C33") (pin "2") (pintype "passive"))
      (node (ref "R16") (pin "1") (pintype "passive"))
      (node (ref "U3") (pin "5") (pinfunction "PD0/OSCIN_5") (pintype "passive"))
      (node (ref "Y2") (pin "1") (pinfunction "OSC1_1") (pintype "passive"))
    )
    (net (code "84") (name "Net-(U3-PD1{slash}OSCOUT)") (class "Default")
      (node (ref "C34") (pin "2") (pintype "passive"))
      (node (ref "R16") (pin "2") (pintype "passive"))
      (node (ref "U3") (pin "6") (pinfunction "PD1/OSCOUT_6") (pintype "passive"))
      (node (ref "Y2") (pin "2") (pinfunction "OSC2_2") (pintype "passive"))
    )
    (net (code "85") (name "Net-(U3-VBAT)") (class "Default")
      (node (ref "D1") (pin "2") (pintype "passive"))
      (node (ref "U3") (pin "1") (pinfunction "VBAT_1") (pintype "passive"))
    )
    (net (code "86") (name "Net-(U3-VDDA)") (class "Default")
      (node (ref "C35") (pin "1") (pintype "passive"))
      (node (ref "C36") (pin "1") (pintype "passive"))
      (node (ref "R17") (pin "2") (pintype "passive"))
      (node (ref "U3") (pin "13") (pinfunction "VDDA_13") (pintype "passive"))
    )
    (net (code "87") (name "Net-(U3-VSSA)") (class "Default")
      (node (ref "C31") (pin "1") (pintype "passive"))
      (node (ref "C32") (pin "1") (pintype "passive"))
      (node (ref "C33") (pin "1") (pintype "passive"))
      (node (ref "C34") (pin "1") (pintype "passive"))
      (node (ref "C35") (pin "2") (pintype "passive"))
      (node (ref "C36") (pin "2") (pintype "passive"))
      (node (ref "U3") (pin "12") (pinfunction "VSSA_12") (pintype "passive"))
    )
    (net (code "88") (name "Net-(U4-V3)") (class "Default")
      (node (ref "C44") (pin "1") (pintype "passive"))
      (node (ref "U4") (pin "4") (pinfunction "V3_4") (pintype "passive"))
    )
    (net (code "89") (name "Net-(U4-XI)") (class "Default")
      (node (ref "C42") (pin "2") (pintype "passive"))
      (node (ref "U4") (pin "7") (pinfunction "XI_7") (pintype "passive"))
      (node (ref "Y3") (pin "1") (pinfunction "OSC1_1") (pintype "passive"))
    )
    (net (code "90") (name "Net-(U4-XO)") (class "Default")
      (node (ref "C43") (pin "2") (pintype "passive"))
      (node (ref "U4") (pin "8") (pinfunction "XO_8") (pintype "passive"))
      (node (ref "Y3") (pin "2") (pinfunction "OSC2_2") (pintype "passive"))
    )
    (net (code "91") (name "Net-(USB_232-GND)") (class "Default")
      (node (ref "F1") (pin "1") (pintype "passive"))
      (node (ref "USB_232") (pin "5") (pinfunction "GND_5") (pintype "passive"))
    )
    (net (code "92") (name "Net-(USB_232-VCC)") (class "Default")
      (node (ref "K1") (pin "3") (pinfunction "I/O1_3") (pintype "passive"))
      (node (ref "K1") (pin "4") (pinfunction "I/O2_4") (pintype "passive"))
      (node (ref "USB_232") (pin "1") (pinfunction "VCC_1") (pintype "passive"))
    )
    (net (code "93") (name "VCC") (class "Default")
      (node (ref "C1") (pin "2") (pintype "passive"))
      (node (ref "C2") (pin "2") (pintype "passive"))
      (node (ref "C27") (pin "2") (pintype "passive"))
      (node (ref "C3") (pin "2") (pintype "passive"))
      (node (ref "C37") (pin "2") (pintype "passive"))
      (node (ref "C38") (pin "1") (pintype "passive"))
      (node (ref "C39") (pin "2") (pintype "passive"))
      (node (ref "C41") (pin "1") (pintype "passive"))
      (node (ref "C45") (pin "2") (pintype "passive"))
      (node (ref "C48") (pin "2") (pintype "passive"))
      (node (ref "C49") (pin "1") (pinfunction "VCC_1") (pintype "passive"))
      (node (ref "C50") (pin "1") (pintype "passive"))
      (node (ref "D1") (pin "1") (pintype "passive"))
      (node (ref "D3") (pin "2") (pintype "passive"))
      (node (ref "D4") (pin "2") (pintype "passive"))
      (node (ref "KEY1") (pin "1") (pinfunction "1_1") (pintype "passive"))
      (node (ref "Q1") (pin "1") (pinfunction "E_1") (pintype "passive"))
      (node (ref "R1") (pin "2") (pintype "passive"))
      (node (ref "R11") (pin "1") (pintype "passive"))
      (node (ref "R17") (pin "1") (pintype "passive"))
      (node (ref "R20") (pin "1") (pintype "passive"))
      (node (ref "R24") (pin "1") (pintype "passive"))
      (node (ref "R25") (pin "1") (pintype "passive"))
      (node (ref "R8") (pin "1") (pintype "passive"))
      (node (ref "SD_CARD") (pin "4") (pinfunction "VDD_4") (pintype "passive"))
      (node (ref "TFTLCD") (pin "24") (pinfunction "VDD3.3_24") (pintype "passive"))
      (node (ref "TFTLCD") (pin "25") (pinfunction "VDD3.3_25") (pintype "passive"))
      (node (ref "U1") (pin "14") (pinfunction "IOVDD_14") (pintype "passive"))
      (node (ref "U1") (pin "19") (pinfunction "IOVDD_19") (pintype "passive"))
      (node (ref "U1") (pin "32") (pinfunction "TEST_32") (pintype "passive"))
      (node (ref "U1") (pin "6") (pinfunction "IOVDD_6") (pintype "passive"))
      (node (ref "U2") (pin "3") (pinfunction "IN_3") (pintype "passive"))
      (node (ref "U3") (pin "19") (pinfunction "VDD_19") (pintype "passive"))
      (node (ref "U3") (pin "32") (pinfunction "VDD_32") (pintype "passive"))
      (node (ref "U3") (pin "48") (pinfunction "VDD_48") (pintype "passive"))
      (node (ref "U3") (pin "64") (pinfunction "VDD_64") (pintype "passive"))
      (node (ref "U5") (pin "3") (pinfunction "WP#_3") (pintype "passive"))
      (node (ref "U5") (pin "7") (pinfunction "HOLD_7") (pintype "passive"))
      (node (ref "U5") (pin "8") (pinfunction "VCC_8") (pintype "passive"))
      (node (ref "U7") (pin "2") (pinfunction "OUT_2") (pintype "passive"))
      (node (ref "U7") (pin "4") (pinfunction "OUT_4") (pintype "passive"))
      (node (ref "kEY0") (pin "1") (pinfunction "1_1") (pintype "passive"))
    )
    (net (code "94") (name "VCC5") (class "Default")
      (node (ref "C40") (pin "1") (pintype "passive"))
      (node (ref "C46") (pin "2") (pintype "passive"))
      (node (ref "C47") (pin "1") (pintype "passive"))
      (node (ref "C51") (pin "1") (pinfunction "VCC_1") (pintype "passive"))
      (node (ref "C52") (pin "1") (pintype "passive"))
      (node (ref "D5") (pin "2") (pintype "passive"))
      (node (ref "K1") (pin "2") (pinfunction "TAP1_2") (pintype "passive"))
      (node (ref "K1") (pin "5") (pinfunction "TAP2_5") (pintype "passive"))
      (node (ref "TFTLCD") (pin "28") (pinfunction "BL_VDD_28") (pintype "passive"))
      (node (ref "U4") (pin "16") (pinfunction "VCC_16") (pintype "passive"))
      (node (ref "U7") (pin "3") (pinfunction "IN_3") (pintype "passive"))
    )
    (net (code "95") (name "unconnected-(K1-I{slash}O1-Pad1)") (class "Default")
      (node (ref "K1") (pin "1") (pinfunction "I/O1_1") (pintype "passive"))
    )
    (net (code "96") (name "unconnected-(K1-I{slash}O2-Pad6)") (class "Default")
      (node (ref "K1") (pin "6") (pinfunction "I/O2_6") (pintype "passive"))
    )
    (net (code "97") (name "unconnected-(SD_CARD-CD-Pad10)") (class "Default")
      (node (ref "SD_CARD") (pin "10") (pinfunction "CD_10") (pintype "passive"))
    )
    (net (code "98") (name "unconnected-(SD_CARD-DATA1-Pad8)") (class "Default")
      (node (ref "SD_CARD") (pin "8") (pinfunction "DATA1_8") (pintype "passive"))
    )
    (net (code "99") (name "unconnected-(SD_CARD-DATA2-Pad9)") (class "Default")
      (node (ref "SD_CARD") (pin "9") (pinfunction "DATA2_9") (pintype "passive"))
    )
    (net (code "100") (name "unconnected-(SD_CARD-GND-Pad11)") (class "Default")
      (node (ref "SD_CARD") (pin "11") (pinfunction "GND_11") (pintype "passive"))
    )
    (net (code "101") (name "unconnected-(SD_CARD-WP-Pad12)") (class "Default")
      (node (ref "SD_CARD") (pin "12") (pinfunction "WP_12") (pintype "passive"))
    )
    (net (code "102") (name "unconnected-(TFTLCD-MO-Pad32)") (class "Default")
      (node (ref "TFTLCD") (pin "32") (pinfunction "MO_32") (pintype "passive"))
    )
    (net (code "103") (name "unconnected-(U1-GPIO2{slash}DCLK-Pad9)") (class "Default")
      (node (ref "U1") (pin "9") (pinfunction "GPIO2/DCLK_9") (pintype "passive"))
    )
    (net (code "104") (name "unconnected-(U1-GPIO3{slash}SDATA-Pad10)") (class "Default")
      (node (ref "U1") (pin "10") (pinfunction "GPIO3/SDATA_10") (pintype "passive"))
    )
    (net (code "105") (name "unconnected-(U1-GPIO4{slash}I2S_LROUT-Pad36)") (class "Default")
      (node (ref "U1") (pin "36") (pinfunction "GPIO4/I2S_LROUT_36") (pintype "passive"))
    )
    (net (code "106") (name "unconnected-(U1-GPIO5{slash}I2S_MCLK-Pad25)") (class "Default")
      (node (ref "U1") (pin "25") (pinfunction "GPIO5/I2S_MCLK_25") (pintype "passive"))
    )
    (net (code "107") (name "unconnected-(U1-GPIO6{slash}I2S_SCLK-Pad11)") (class "Default")
      (node (ref "U1") (pin "11") (pinfunction "GPIO6/I2S_SCLK_11") (pintype "passive"))
    )
    (net (code "108") (name "unconnected-(U1-GPIO7{slash}I2S_SDATA-Pad12)") (class "Default")
      (node (ref "U1") (pin "12") (pinfunction "GPIO7/I2S_SDATA_12") (pintype "passive"))
    )
    (net (code "109") (name "unconnected-(U1-TX-Pad27)") (class "Default")
      (node (ref "U1") (pin "27") (pinfunction "TX_27") (pintype "passive"))
    )
    (net (code "110") (name "unconnected-(U1-VCO-Pad15)") (class "Default")
      (node (ref "U1") (pin "15") (pinfunction "VCO_15") (pintype "passive"))
    )
    (net (code "111") (name "unconnected-(U3-PA0{slash}WKUP{slash}ADC0{slash}TIM2_CH1_ETR{slash}TIM5_CH1{slash}TIM8_ETR-Pad14)") (class "Default")
      (node (ref "U3") (pin "14") (pinfunction "PA0/WKUP/ADC0/TIM2_CH1_ETR/TIM5_CH1/TIM8_ETR_14") (pintype "passive"))
    )
    (net (code "112") (name "unconnected-(U3-PA1{slash}ADC1{slash}TIM2_CH2{slash}TIM5_CH2-Pad15)") (class "Default")
      (node (ref "U3") (pin "15") (pinfunction "PA1/ADC1/TIM2_CH2/TIM5_CH2_15") (pintype "passive"))
    )
    (net (code "113") (name "unconnected-(U3-PA4{slash}SPI1_NSS{slash}ADC4{slash}DAC1-Pad20)") (class "Default")
      (node (ref "U3") (pin "20") (pinfunction "PA4/SPI1_NSS/ADC4/DAC1_20") (pintype "passive"))
    )
    (net (code "114") (name "unconnected-(U3-PA13{slash}JTMS{slash}SWDIO-Pad46)") (class "Default")
      (node (ref "U3") (pin "46") (pinfunction "PA13/JTMS/SWDIO_46") (pintype "passive"))
    )
    (net (code "115") (name "unconnected-(U3-PA14{slash}JTCK{slash}SWCLK-Pad49)") (class "Default")
      (node (ref "U3") (pin "49") (pinfunction "PA14/JTCK/SWCLK_49") (pintype "passive"))
    )
    (net (code "116") (name "unconnected-(U3-PA15{slash}JTDI{slash}SPI3_NSS{slash}I2S3_WS-Pad50)") (class "Default")
      (node (ref "U3") (pin "50") (pinfunction "PA15/JTDI/SPI3_NSS/I2S3_WS_50") (pintype "passive"))
    )
    (net (code "117") (name "unconnected-(U3-PC4{slash}ADC14-Pad24)") (class "Default")
      (node (ref "U3") (pin "24") (pinfunction "PC4/ADC14_24") (pintype "passive"))
    )
    (net (code "118") (name "unconnected-(U3-PC5{slash}ADC15-Pad25)") (class "Default")
      (node (ref "U3") (pin "25") (pinfunction "PC5/ADC15_25") (pintype "passive"))
    )
    (net (code "119") (name "unconnected-(U3-PC13{slash}ANT1-Pad2)") (class "Default")
      (node (ref "U3") (pin "2") (pinfunction "PC13/ANT1_2") (pintype "passive"))
    )
    (net (code "120") (name "unconnected-(U4-CTS#-Pad9)") (class "Default")
      (node (ref "U4") (pin "9") (pinfunction "CTS#_9") (pintype "passive"))
    )
    (net (code "121") (name "unconnected-(U4-DCD#-Pad12)") (class "Default")
      (node (ref "U4") (pin "12") (pinfunction "DCD#_12") (pintype "passive"))
    )
    (net (code "122") (name "unconnected-(U4-DSR#-Pad10)") (class "Default")
      (node (ref "U4") (pin "10") (pinfunction "DSR#_10") (pintype "passive"))
    )
    (net (code "123") (name "unconnected-(U4-R232-Pad15)") (class "Default")
      (node (ref "U4") (pin "15") (pinfunction "R232_15") (pintype "passive"))
    )
    (net (code "124") (name "unconnected-(U4-RI#-Pad11)") (class "Default")
      (node (ref "U4") (pin "11") (pinfunction "RI#_11") (pintype "passive"))
    )
    (net (code "125") (name "unconnected-(U6-GND-Pad1)") (class "Default")
      (node (ref "U6") (pin "1") (pinfunction "GND_1") (pintype "passive"))
    )
    (net (code "126") (name "unconnected-(U6-IN-Pad3)") (class "Default")
      (node (ref "U6") (pin "3") (pinfunction "IN_3") (pintype "passive"))
    )
    (net (code "127") (name "unconnected-(U6-OUT-Pad2)") (class "Default")
      (node (ref "U6") (pin "2") (pinfunction "OUT_2") (pintype "passive"))
    )
    (net (code "128") (name "unconnected-(U6-OUT-Pad4)") (class "Default")
      (node (ref "U6") (pin "4") (pinfunction "OUT_4") (pintype "passive"))
    )
    (net (code "129") (name "unconnected-(USB_232-NC-Pad4)") (class "Default")
      (node (ref "USB_232") (pin "4") (pinfunction "NC_4") (pintype "passive"))
    )
  )
)
